# ethernet.net
KiCad netlist of a schematic drawn in Altium Designer
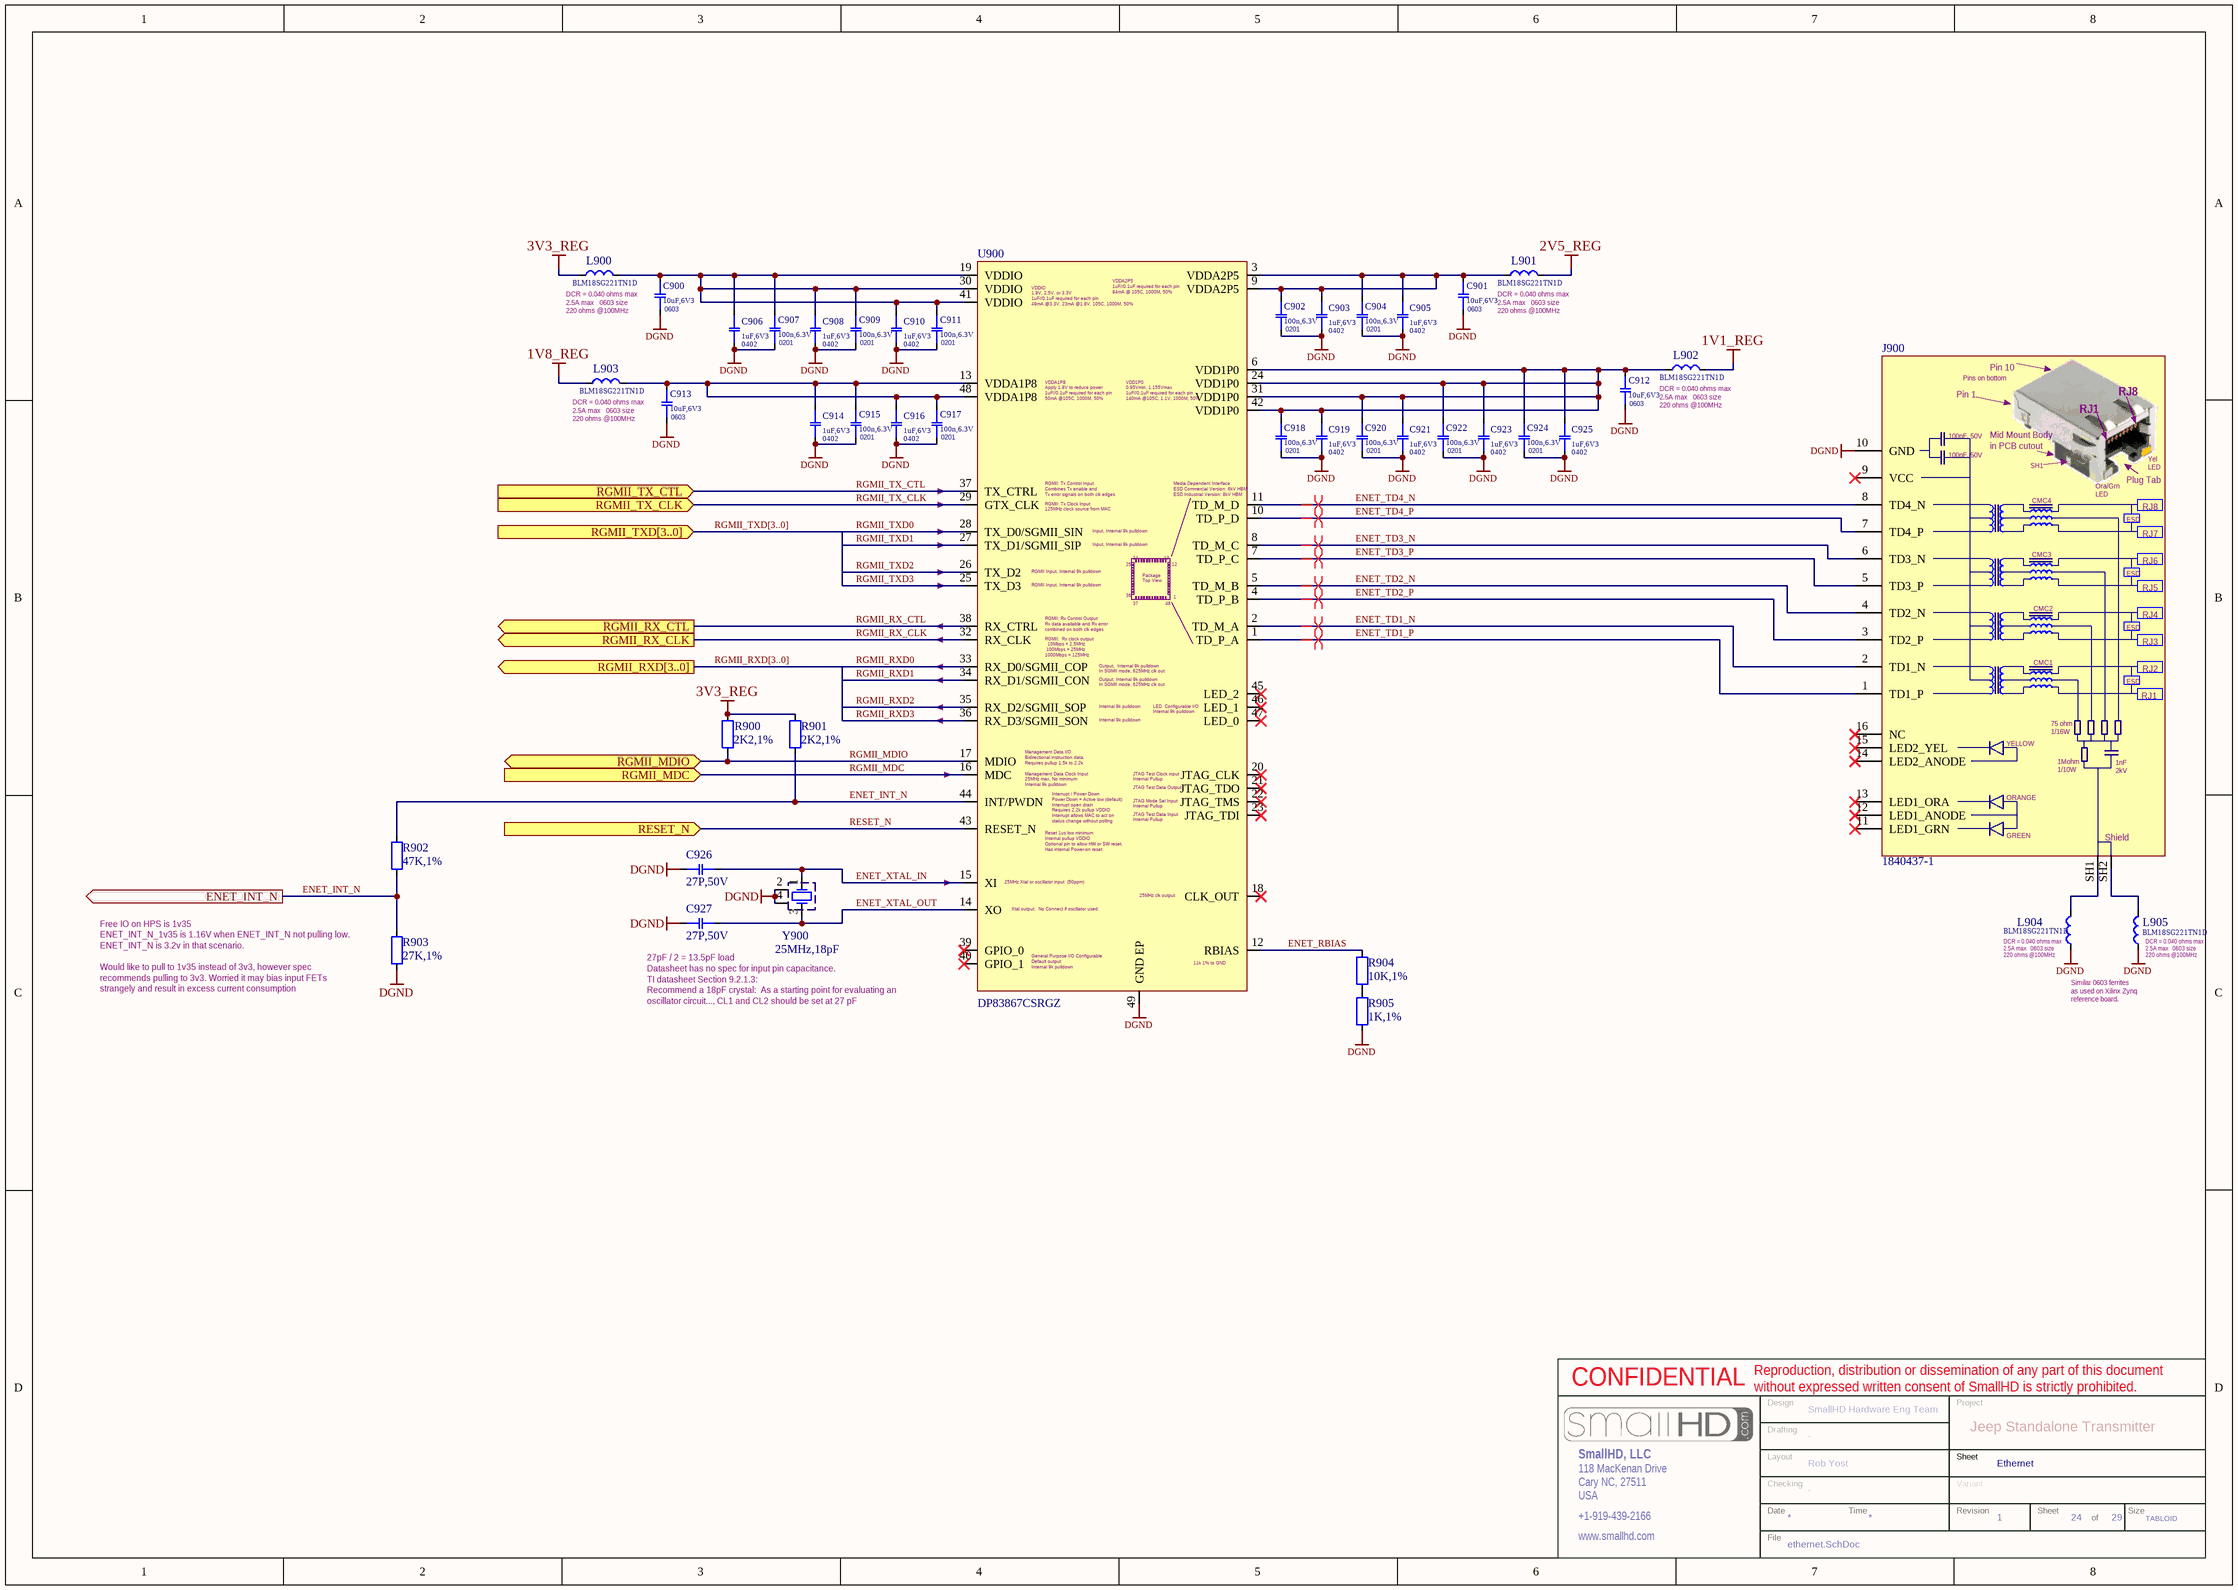
[diagram p0: ethernet.SchDoc]

(export (version "E")
  (design (tool "Eeschema 10.0.6"))
  (components
    (comp (ref "C900")
      (value "10uF,6V3")
      (footprint "CAPC1608X10N_0603")
      (description "CAP CER 10UF 6.3V 20% X5R 0603")
      (fields
        (field (name "MANUFACTURER") "TDK")
        (field (name "TOLERANCE") "20%")
        (field (name "DISPLAY FOOTPRINT") "0603")
      )
      (libsource (lib "smallHD") (part "CAP-NP_1"))
    )
    (comp (ref "C901")
      (value "10uF,6V3")
      (footprint "CAPC1608X10N_0603")
      (description "CAP CER 10UF 6.3V 20% X5R 0603")
      (fields
        (field (name "MANUFACTURER") "TDK")
        (field (name "TOLERANCE") "20%")
        (field (name "DISPLAY FOOTPRINT") "0603")
      )
      (libsource (lib "smallHD") (part "CAP-NP_1"))
    )
    (comp (ref "C902")
      (value "100n,6.3V")
      (footprint "CAPC0603X03L_0201")
      (description "CAP CER 0.1UF 6.3V 20% X5R 0201")
      (fields
        (field (name "MANUFACTURER") "TDK")
        (field (name "TOLERANCE") "20%")
        (field (name "DISPLAY FOOTPRINT") "0201")
      )
      (libsource (lib "smallHD") (part "CAP-NP_1"))
    )
    (comp (ref "C903")
      (value "1uF,6V3")
      (footprint "CAPC1005X06N_0402")
      (description "CAP CER 1UF 6.3V 10% X5R 0402")
      (fields
        (field (name "MANUFACTURER") "AVX")
        (field (name "TOLERANCE") "10%")
        (field (name "DISPLAY FOOTPRINT") "0402")
      )
      (libsource (lib "smallHD") (part "CAP-NP_1"))
    )
    (comp (ref "C904")
      (value "100n,6.3V")
      (footprint "CAPC0603X03L_0201")
      (description "CAP CER 0.1UF 6.3V 20% X5R 0201")
      (fields
        (field (name "MANUFACTURER") "TDK")
        (field (name "TOLERANCE") "20%")
        (field (name "DISPLAY FOOTPRINT") "0201")
      )
      (libsource (lib "smallHD") (part "CAP-NP_1"))
    )
    (comp (ref "C905")
      (value "1uF,6V3")
      (footprint "CAPC1005X06N_0402")
      (description "CAP CER 1UF 6.3V 10% X5R 0402")
      (fields
        (field (name "MANUFACTURER") "AVX")
        (field (name "TOLERANCE") "10%")
        (field (name "DISPLAY FOOTPRINT") "0402")
      )
      (libsource (lib "smallHD") (part "CAP-NP_1"))
    )
    (comp (ref "C906")
      (value "1uF,6V3")
      (footprint "CAPC1005X06N_0402")
      (description "CAP CER 1UF 6.3V 10% X5R 0402")
      (fields
        (field (name "MANUFACTURER") "AVX")
        (field (name "TOLERANCE") "10%")
        (field (name "DISPLAY FOOTPRINT") "0402")
      )
      (libsource (lib "smallHD") (part "CAP-NP_1"))
    )
    (comp (ref "C907")
      (value "100n,6.3V")
      (footprint "CAPC0603X03L_0201")
      (description "CAP CER 0.1UF 6.3V 20% X5R 0201")
      (fields
        (field (name "MANUFACTURER") "TDK")
        (field (name "TOLERANCE") "20%")
        (field (name "DISPLAY FOOTPRINT") "0201")
      )
      (libsource (lib "smallHD") (part "CAP-NP_1"))
    )
    (comp (ref "C908")
      (value "1uF,6V3")
      (footprint "CAPC1005X06N_0402")
      (description "CAP CER 1UF 6.3V 10% X5R 0402")
      (fields
        (field (name "MANUFACTURER") "AVX")
        (field (name "TOLERANCE") "10%")
        (field (name "DISPLAY FOOTPRINT") "0402")
      )
      (libsource (lib "smallHD") (part "CAP-NP_1"))
    )
    (comp (ref "C909")
      (value "100n,6.3V")
      (footprint "CAPC0603X03L_0201")
      (description "CAP CER 0.1UF 6.3V 20% X5R 0201")
      (fields
        (field (name "MANUFACTURER") "TDK")
        (field (name "TOLERANCE") "20%")
        (field (name "DISPLAY FOOTPRINT") "0201")
      )
      (libsource (lib "smallHD") (part "CAP-NP_1"))
    )
    (comp (ref "C910")
      (value "1uF,6V3")
      (footprint "CAPC1005X06N_0402")
      (description "CAP CER 1UF 6.3V 10% X5R 0402")
      (fields
        (field (name "MANUFACTURER") "AVX")
        (field (name "TOLERANCE") "10%")
        (field (name "DISPLAY FOOTPRINT") "0402")
      )
      (libsource (lib "smallHD") (part "CAP-NP_1"))
    )
    (comp (ref "C911")
      (value "100n,6.3V")
      (footprint "CAPC0603X03L_0201")
      (description "CAP CER 0.1UF 6.3V 20% X5R 0201")
      (fields
        (field (name "MANUFACTURER") "TDK")
        (field (name "TOLERANCE") "20%")
        (field (name "DISPLAY FOOTPRINT") "0201")
      )
      (libsource (lib "smallHD") (part "CAP-NP_1"))
    )
    (comp (ref "C912")
      (value "10uF,6V3")
      (footprint "CAPC1608X10N_0603")
      (description "CAP CER 10UF 6.3V 20% X5R 0603")
      (fields
        (field (name "MANUFACTURER") "TDK")
        (field (name "TOLERANCE") "20%")
        (field (name "DISPLAY FOOTPRINT") "0603")
      )
      (libsource (lib "smallHD") (part "CAP-NP_1"))
    )
    (comp (ref "C913")
      (value "10uF,6V3")
      (footprint "CAPC1608X10N_0603")
      (description "CAP CER 10UF 6.3V 20% X5R 0603")
      (fields
        (field (name "MANUFACTURER") "TDK")
        (field (name "TOLERANCE") "20%")
        (field (name "DISPLAY FOOTPRINT") "0603")
      )
      (libsource (lib "smallHD") (part "CAP-NP_1"))
    )
    (comp (ref "C914")
      (value "1uF,6V3")
      (footprint "CAPC1005X06N_0402")
      (description "CAP CER 1UF 6.3V 10% X5R 0402")
      (fields
        (field (name "MANUFACTURER") "AVX")
        (field (name "TOLERANCE") "10%")
        (field (name "DISPLAY FOOTPRINT") "0402")
      )
      (libsource (lib "smallHD") (part "CAP-NP_1"))
    )
    (comp (ref "C915")
      (value "100n,6.3V")
      (footprint "CAPC0603X03L_0201")
      (description "CAP CER 0.1UF 6.3V 20% X5R 0201")
      (fields
        (field (name "MANUFACTURER") "TDK")
        (field (name "TOLERANCE") "20%")
        (field (name "DISPLAY FOOTPRINT") "0201")
      )
      (libsource (lib "smallHD") (part "CAP-NP_1"))
    )
    (comp (ref "C916")
      (value "1uF,6V3")
      (footprint "CAPC1005X06N_0402")
      (description "CAP CER 1UF 6.3V 10% X5R 0402")
      (fields
        (field (name "MANUFACTURER") "AVX")
        (field (name "TOLERANCE") "10%")
        (field (name "DISPLAY FOOTPRINT") "0402")
      )
      (libsource (lib "smallHD") (part "CAP-NP_1"))
    )
    (comp (ref "C917")
      (value "100n,6.3V")
      (footprint "CAPC0603X03L_0201")
      (description "CAP CER 0.1UF 6.3V 20% X5R 0201")
      (fields
        (field (name "MANUFACTURER") "TDK")
        (field (name "TOLERANCE") "20%")
        (field (name "DISPLAY FOOTPRINT") "0201")
      )
      (libsource (lib "smallHD") (part "CAP-NP_1"))
    )
    (comp (ref "C918")
      (value "100n,6.3V")
      (footprint "CAPC0603X03L_0201")
      (description "CAP CER 0.1UF 6.3V 20% X5R 0201")
      (fields
        (field (name "MANUFACTURER") "TDK")
        (field (name "TOLERANCE") "20%")
        (field (name "DISPLAY FOOTPRINT") "0201")
      )
      (libsource (lib "smallHD") (part "CAP-NP_1"))
    )
    (comp (ref "C919")
      (value "1uF,6V3")
      (footprint "CAPC1005X06N_0402")
      (description "CAP CER 1UF 6.3V 10% X5R 0402")
      (fields
        (field (name "MANUFACTURER") "AVX")
        (field (name "TOLERANCE") "10%")
        (field (name "DISPLAY FOOTPRINT") "0402")
      )
      (libsource (lib "smallHD") (part "CAP-NP_1"))
    )
    (comp (ref "C920")
      (value "100n,6.3V")
      (footprint "CAPC0603X03L_0201")
      (description "CAP CER 0.1UF 6.3V 20% X5R 0201")
      (fields
        (field (name "MANUFACTURER") "TDK")
        (field (name "TOLERANCE") "20%")
        (field (name "DISPLAY FOOTPRINT") "0201")
      )
      (libsource (lib "smallHD") (part "CAP-NP_1"))
    )
    (comp (ref "C921")
      (value "1uF,6V3")
      (footprint "CAPC1005X06N_0402")
      (description "CAP CER 1UF 6.3V 10% X5R 0402")
      (fields
        (field (name "MANUFACTURER") "AVX")
        (field (name "TOLERANCE") "10%")
        (field (name "DISPLAY FOOTPRINT") "0402")
      )
      (libsource (lib "smallHD") (part "CAP-NP_1"))
    )
    (comp (ref "C922")
      (value "100n,6.3V")
      (footprint "CAPC0603X03L_0201")
      (description "CAP CER 0.1UF 6.3V 20% X5R 0201")
      (fields
        (field (name "MANUFACTURER") "TDK")
        (field (name "TOLERANCE") "20%")
        (field (name "DISPLAY FOOTPRINT") "0201")
      )
      (libsource (lib "smallHD") (part "CAP-NP_1"))
    )
    (comp (ref "C923")
      (value "1uF,6V3")
      (footprint "CAPC1005X06N_0402")
      (description "CAP CER 1UF 6.3V 10% X5R 0402")
      (fields
        (field (name "MANUFACTURER") "AVX")
        (field (name "TOLERANCE") "10%")
        (field (name "DISPLAY FOOTPRINT") "0402")
      )
      (libsource (lib "smallHD") (part "CAP-NP_1"))
    )
    (comp (ref "C924")
      (value "100n,6.3V")
      (footprint "CAPC0603X03L_0201")
      (description "CAP CER 0.1UF 6.3V 20% X5R 0201")
      (fields
        (field (name "MANUFACTURER") "TDK")
        (field (name "TOLERANCE") "20%")
        (field (name "DISPLAY FOOTPRINT") "0201")
      )
      (libsource (lib "smallHD") (part "CAP-NP_1"))
    )
    (comp (ref "C925")
      (value "1uF,6V3")
      (footprint "CAPC1005X06N_0402")
      (description "CAP CER 1UF 6.3V 10% X5R 0402")
      (fields
        (field (name "MANUFACTURER") "AVX")
        (field (name "TOLERANCE") "10%")
        (field (name "DISPLAY FOOTPRINT") "0402")
      )
      (libsource (lib "smallHD") (part "CAP-NP_1"))
    )
    (comp (ref "C926")
      (value "27P,50V")
      (footprint "CAPC0603X03L_0201")
      (description "CAP CER 27PF 50V 5% NPO 0201")
      (fields (field (name "MANUFACTURER") "Murata") (field (name "TOLERANCE") "5%"))
      (libsource (lib "smallHD") (part "CAP-NP_1"))
    )
    (comp (ref "C927")
      (value "27P,50V")
      (footprint "CAPC0603X03L_0201")
      (description "CAP CER 27PF 50V 5% NPO 0201")
      (fields (field (name "MANUFACTURER") "Murata") (field (name "TOLERANCE") "5%"))
      (libsource (lib "smallHD") (part "CAP-NP_1"))
    )
    (comp (ref "J900")
      (value "1840437-1")
      (footprint "BEL_1840437-1")
      (description "CONN RJ45 MAGJACK 1PORT 1000 BASE-T")
      (fields (field (name "MANUFACTURER") "Bel Fuse, Inc."))
      (libsource (lib "smallHD") (part "Bel_1840437-1"))
    )
    (comp (ref "L900")
      (value "BLM18SG221TN1D​")
      (footprint "INDC1608X10N_0603")
      (description "FERRITE CHIP 220 OHM 2.5A 0603")
      (fields (field (name "MANUFACTURER") "Murata"))
      (libsource (lib "smallHD") (part "INDUCTOR_1"))
    )
    (comp (ref "L901")
      (value "BLM18SG221TN1D​")
      (footprint "INDC1608X10N_0603")
      (description "FERRITE CHIP 220 OHM 2.5A 0603")
      (fields (field (name "MANUFACTURER") "Murata"))
      (libsource (lib "smallHD") (part "INDUCTOR_1"))
    )
    (comp (ref "L902")
      (value "BLM18SG221TN1D​")
      (footprint "INDC1608X10N_0603")
      (description "FERRITE CHIP 220 OHM 2.5A 0603")
      (fields (field (name "MANUFACTURER") "Murata"))
      (libsource (lib "smallHD") (part "INDUCTOR_1"))
    )
    (comp (ref "L903")
      (value "BLM18SG221TN1D​")
      (footprint "INDC1608X10N_0603")
      (description "FERRITE CHIP 220 OHM 2.5A 0603")
      (fields (field (name "MANUFACTURER") "Murata"))
      (libsource (lib "smallHD") (part "INDUCTOR_1"))
    )
    (comp (ref "L904")
      (value "BLM18SG221TN1D​")
      (footprint "INDC1608X10N_0603")
      (description "FERRITE CHIP 220 OHM 2.5A 0603")
      (fields (field (name "MANUFACTURER") "Murata"))
      (libsource (lib "smallHD") (part "INDUCTOR_1"))
    )
    (comp (ref "L905")
      (value "BLM18SG221TN1D​")
      (footprint "INDC1608X10N_0603")
      (description "FERRITE CHIP 220 OHM 2.5A 0603")
      (fields (field (name "MANUFACTURER") "Murata"))
      (libsource (lib "smallHD") (part "INDUCTOR_1"))
    )
    (comp (ref "R900")
      (value "2K2,1%")
      (footprint "RESC1005X04N_0402")
      (description "RES SMD 2.2K OHM 1/16W 1% 0402")
      (fields (field (name "MANUFACTURER") "Yageo") (field (name "POWER") "0.0625W"))
      (libsource (lib "smallHD") (part "RESISTOR_1"))
    )
    (comp (ref "R901")
      (value "2K2,1%")
      (footprint "RESC1005X04N_0402")
      (description "RES SMD 2.2K OHM 1/16W 1% 0402")
      (fields (field (name "MANUFACTURER") "Yageo") (field (name "POWER") "0.0625W"))
      (libsource (lib "smallHD") (part "RESISTOR_1"))
    )
    (comp (ref "R902")
      (value "47K,1%")
      (footprint "RESC1005X04N_0402")
      (description "RES SMD 47K OHM 1/16W 1% 0402")
      (fields (field (name "MANUFACTURER") "Yageo") (field (name "POWER") "0.0625W"))
      (libsource (lib "smallHD") (part "RESISTOR_1"))
    )
    (comp (ref "R903")
      (value "27K,1%")
      (footprint "RESC1005X04N_0402")
      (description "RES SMD 27K OHM 1/16W 1% 0402")
      (fields (field (name "MANUFACTURER") "Yageo") (field (name "POWER") "0.0625W"))
      (libsource (lib "smallHD") (part "RESISTOR_1"))
    )
    (comp (ref "R904")
      (value "10K,1%")
      (footprint "RESC1005X04N_0402")
      (description "RES SMD 10K OHM 1/16W 1% 0402")
      (fields (field (name "MANUFACTURER") "Yageo") (field (name "POWER") "0.0625W"))
      (libsource (lib "smallHD") (part "RESISTOR_1"))
    )
    (comp (ref "R905")
      (value "1K,1%")
      (footprint "RESC1005X04N_0402")
      (description "RES SMD 1K OHM 1/16W 1% 0402")
      (fields (field (name "MANUFACTURER") "Yageo") (field (name "POWER") "0.0625W"))
      (libsource (lib "") (part "RESISTOR_1_1"))
    )
    (comp (ref "U900")
      (value "DP83867CSRGZ")
      (footprint "QFN50P700X700X100_HS-49N")
      (description "IC ETHERNET PHY 10/100/1000 RGMII SGMII 48VQFN")
      (fields
        (field (name "MANUFACTURER") "Texas Instruments")
        (field (name "MANUFACTURER-2 PART NUMBER") "DP83867ISRGZ")
      )
      (libsource (lib "smallHD") (part "DP83867CS"))
    )
    (comp (ref "Y900")
      (value "25MHz,18pF")
      (footprint "XTAL_ABM8")
      (description "CRYSTAL 25.000MHZ 18PF SMD")
      (fields
        (field (name "MANUFACTURER") "Abracon Corporation")
        (field (name "MANUFACTURER PART NUMBER") "ABM8-25.000MHZ-B2-T")
      )
      (libsource (lib "smallHD") (part "XTAL_2"))
    )
  )
  (nets
    (net (code "1") (name "/ENET_INT_N") (class "Default")
      (node (ref "R901") (pin "1") (pinfunction "1_1") (pintype "passive"))
      (node (ref "R902") (pin "1") (pinfunction "1_1") (pintype "passive"))
      (node (ref "R902") (pin "2") (pinfunction "2_2") (pintype "passive"))
      (node (ref "R903") (pin "2") (pinfunction "2_2") (pintype "passive"))
      (node (ref "U900") (pin "44") (pinfunction "INT/PWDN_44") (pintype "passive"))
    )
    (net (code "2") (name "/ENET_RBIAS") (class "Default")
      (node (ref "R904") (pin "2") (pinfunction "2_2") (pintype "passive"))
      (node (ref "U900") (pin "12") (pinfunction "RBIAS_12") (pintype "passive"))
    )
    (net (code "3") (name "/ENET_TD1_N") (class "Default")
      (node (ref "J900") (pin "2") (pinfunction "TD1_N_2") (pintype "passive"))
      (node (ref "U900") (pin "2") (pinfunction "TD_M_A_2") (pintype "passive"))
    )
    (net (code "4") (name "/ENET_TD1_P") (class "Default")
      (node (ref "J900") (pin "1") (pinfunction "TD1_P_1") (pintype "passive"))
      (node (ref "U900") (pin "1") (pinfunction "TD_P_A_1") (pintype "passive"))
    )
    (net (code "5") (name "/ENET_TD2_N") (class "Default")
      (node (ref "J900") (pin "4") (pinfunction "TD2_N_4") (pintype "passive"))
      (node (ref "U900") (pin "5") (pinfunction "TD_M_B_5") (pintype "passive"))
    )
    (net (code "6") (name "/ENET_TD2_P") (class "Default")
      (node (ref "J900") (pin "3") (pinfunction "TD2_P_3") (pintype "passive"))
      (node (ref "U900") (pin "4") (pinfunction "TD_P_B_4") (pintype "passive"))
    )
    (net (code "7") (name "/ENET_TD3_N") (class "Default")
      (node (ref "J900") (pin "6") (pinfunction "TD3_N_6") (pintype "passive"))
      (node (ref "U900") (pin "8") (pinfunction "TD_M_C_8") (pintype "passive"))
    )
    (net (code "8") (name "/ENET_TD3_P") (class "Default")
      (node (ref "J900") (pin "5") (pinfunction "TD3_P_5") (pintype "passive"))
      (node (ref "U900") (pin "7") (pinfunction "TD_P_C_7") (pintype "passive"))
    )
    (net (code "9") (name "/ENET_TD4_N") (class "Default")
      (node (ref "J900") (pin "8") (pinfunction "TD4_N_8") (pintype "passive"))
      (node (ref "U900") (pin "11") (pinfunction "TD_M_D_11") (pintype "passive"))
    )
    (net (code "10") (name "/ENET_TD4_P") (class "Default")
      (node (ref "J900") (pin "7") (pinfunction "TD4_P_7") (pintype "passive"))
      (node (ref "U900") (pin "10") (pinfunction "TD_P_D_10") (pintype "passive"))
    )
    (net (code "11") (name "/ENET_XTAL_IN") (class "Default")
      (node (ref "C926") (pin "2") (pinfunction "2_2") (pintype "passive"))
      (node (ref "U900") (pin "15") (pinfunction "XI_15") (pintype "passive"))
      (node (ref "Y900") (pin "1") (pinfunction "1_1") (pintype "passive"))
    )
    (net (code "12") (name "/ENET_XTAL_OUT") (class "Default")
      (node (ref "C927") (pin "2") (pinfunction "2_2") (pintype "passive"))
      (node (ref "U900") (pin "14") (pinfunction "XO_14") (pintype "passive"))
      (node (ref "Y900") (pin "3") (pinfunction "3_3") (pintype "passive"))
    )
    (net (code "13") (name "/RESET_N") (class "Default")
      (node (ref "U900") (pin "43") (pinfunction "RESET_N_43") (pintype "passive"))
    )
    (net (code "14") (name "/RGMII_MDC") (class "Default")
      (node (ref "U900") (pin "16") (pinfunction "MDC_16") (pintype "passive"))
    )
    (net (code "15") (name "/RGMII_MDIO") (class "Default")
      (node (ref "R900") (pin "1") (pinfunction "1_1") (pintype "passive"))
      (node (ref "U900") (pin "17") (pinfunction "MDIO_17") (pintype "passive"))
    )
    (net (code "16") (name "/RGMII_RXD0") (class "Default")
      (node (ref "U900") (pin "33") (pinfunction "RX_D0/SGMII_COP_33") (pintype "passive"))
    )
    (net (code "17") (name "/RGMII_RXD1") (class "Default")
      (node (ref "U900") (pin "34") (pinfunction "RX_D1/SGMII_CON_34") (pintype "passive"))
    )
    (net (code "18") (name "/RGMII_RXD2") (class "Default")
      (node (ref "U900") (pin "35") (pinfunction "RX_D2/SGMII_SOP_35") (pintype "passive"))
    )
    (net (code "19") (name "/RGMII_RXD3") (class "Default")
      (node (ref "U900") (pin "36") (pinfunction "RX_D3/SGMII_SON_36") (pintype "passive"))
    )
    (net (code "21") (name "/RGMII_RX_CLK") (class "Default")
      (node (ref "U900") (pin "32") (pinfunction "RX_CLK_32") (pintype "passive"))
    )
    (net (code "22") (name "/RGMII_RX_CTL") (class "Default")
      (node (ref "U900") (pin "38") (pinfunction "RX_CTRL_38") (pintype "passive"))
    )
    (net (code "23") (name "/RGMII_TXD0") (class "Default")
      (node (ref "U900") (pin "28") (pinfunction "TX_D0/SGMII_SIN_28") (pintype "passive"))
    )
    (net (code "24") (name "/RGMII_TXD1") (class "Default")
      (node (ref "U900") (pin "27") (pinfunction "TX_D1/SGMII_SIP_27") (pintype "passive"))
    )
    (net (code "25") (name "/RGMII_TXD2") (class "Default")
      (node (ref "U900") (pin "26") (pinfunction "TX_D2_26") (pintype "passive"))
    )
    (net (code "26") (name "/RGMII_TXD3") (class "Default")
      (node (ref "U900") (pin "25") (pinfunction "TX_D3_25") (pintype "passive"))
    )
    (net (code "28") (name "/RGMII_TX_CLK") (class "Default")
      (node (ref "U900") (pin "29") (pinfunction "GTX_CLK_29") (pintype "passive"))
    )
    (net (code "29") (name "/RGMII_TX_CTL") (class "Default")
      (node (ref "U900") (pin "37") (pinfunction "TX_CTRL_37") (pintype "passive"))
    )
    (net (code "30") (name "1V1_REG") (class "Default")
      (node (ref "L902") (pin "2") (pinfunction "2_2") (pintype "passive"))
    )
    (net (code "31") (name "1V8_REG") (class "Default")
      (node (ref "L903") (pin "1") (pinfunction "1_1") (pintype "passive"))
    )
    (net (code "32") (name "2V5_REG") (class "Default")
      (node (ref "L901") (pin "2") (pinfunction "2_2") (pintype "passive"))
    )
    (net (code "33") (name "3V3_REG") (class "Default")
      (node (ref "L900") (pin "1") (pinfunction "1_1") (pintype "passive"))
      (node (ref "R900") (pin "2") (pinfunction "2_2") (pintype "passive"))
      (node (ref "R901") (pin "2") (pinfunction "2_2") (pintype "passive"))
    )
    (net (code "34") (name "DGND") (class "Default")
      (node (ref "C900") (pin "1") (pinfunction "1_1") (pintype "passive"))
      (node (ref "C901") (pin "1") (pinfunction "1_1") (pintype "passive"))
      (node (ref "C902") (pin "1") (pinfunction "1_1") (pintype "passive"))
      (node (ref "C903") (pin "1") (pinfunction "1_1") (pintype "passive"))
      (node (ref "C904") (pin "1") (pinfunction "1_1") (pintype "passive"))
      (node (ref "C905") (pin "1") (pinfunction "1_1") (pintype "passive"))
      (node (ref "C906") (pin "1") (pinfunction "1_1") (pintype "passive"))
      (node (ref "C907") (pin "1") (pinfunction "1_1") (pintype "passive"))
      (node (ref "C908") (pin "1") (pinfunction "1_1") (pintype "passive"))
      (node (ref "C909") (pin "1") (pinfunction "1_1") (pintype "passive"))
      (node (ref "C910") (pin "1") (pinfunction "1_1") (pintype "passive"))
      (node (ref "C911") (pin "1") (pinfunction "1_1") (pintype "passive"))
      (node (ref "C912") (pin "1") (pinfunction "1_1") (pintype "passive"))
      (node (ref "C913") (pin "1") (pinfunction "1_1") (pintype "passive"))
      (node (ref "C914") (pin "1") (pinfunction "1_1") (pintype "passive"))
      (node (ref "C915") (pin "1") (pinfunction "1_1") (pintype "passive"))
      (node (ref "C916") (pin "1") (pinfunction "1_1") (pintype "passive"))
      (node (ref "C917") (pin "1") (pinfunction "1_1") (pintype "passive"))
      (node (ref "C918") (pin "1") (pinfunction "1_1") (pintype "passive"))
      (node (ref "C919") (pin "1") (pinfunction "1_1") (pintype "passive"))
      (node (ref "C920") (pin "1") (pinfunction "1_1") (pintype "passive"))
      (node (ref "C921") (pin "1") (pinfunction "1_1") (pintype "passive"))
      (node (ref "C922") (pin "1") (pinfunction "1_1") (pintype "passive"))
      (node (ref "C923") (pin "1") (pinfunction "1_1") (pintype "passive"))
      (node (ref "C924") (pin "1") (pinfunction "1_1") (pintype "passive"))
      (node (ref "C925") (pin "1") (pinfunction "1_1") (pintype "passive"))
      (node (ref "C926") (pin "1") (pinfunction "1_1") (pintype "passive"))
      (node (ref "C927") (pin "1") (pinfunction "1_1") (pintype "passive"))
      (node (ref "J900") (pin "10") (pinfunction "GND_10") (pintype "passive"))
      (node (ref "L904") (pin "1") (pinfunction "1_1") (pintype "passive"))
      (node (ref "L905") (pin "1") (pinfunction "1_1") (pintype "passive"))
      (node (ref "R903") (pin "1") (pinfunction "1_1") (pintype "passive"))
      (node (ref "R905") (pin "2") (pinfunction "2_2") (pintype "passive"))
      (node (ref "U900") (pin "49") (pinfunction "GND_EP_49") (pintype "passive"))
      (node (ref "Y900") (pin "2") (pinfunction "2_2") (pintype "passive"))
      (node (ref "Y900") (pin "4") (pinfunction "4_4") (pintype "passive"))
    )
    (net (code "35") (name "Net-(C900-Pad2)") (class "Default")
      (node (ref "C900") (pin "2") (pinfunction "2_2") (pintype "passive"))
      (node (ref "C906") (pin "2") (pinfunction "2_2") (pintype "passive"))
      (node (ref "C907") (pin "2") (pinfunction "2_2") (pintype "passive"))
      (node (ref "C908") (pin "2") (pinfunction "2_2") (pintype "passive"))
      (node (ref "C909") (pin "2") (pinfunction "2_2") (pintype "passive"))
      (node (ref "C910") (pin "2") (pinfunction "2_2") (pintype "passive"))
      (node (ref "C911") (pin "2") (pinfunction "2_2") (pintype "passive"))
      (node (ref "L900") (pin "2") (pinfunction "2_2") (pintype "passive"))
      (node (ref "U900") (pin "19") (pinfunction "VDDIO_19") (pintype "passive"))
      (node (ref "U900") (pin "30") (pinfunction "VDDIO_30") (pintype "passive"))
      (node (ref "U900") (pin "41") (pinfunction "VDDIO_41") (pintype "passive"))
    )
    (net (code "36") (name "Net-(C901-Pad2)") (class "Default")
      (node (ref "C901") (pin "2") (pinfunction "2_2") (pintype "passive"))
      (node (ref "C902") (pin "2") (pinfunction "2_2") (pintype "passive"))
      (node (ref "C903") (pin "2") (pinfunction "2_2") (pintype "passive"))
      (node (ref "C904") (pin "2") (pinfunction "2_2") (pintype "passive"))
      (node (ref "C905") (pin "2") (pinfunction "2_2") (pintype "passive"))
      (node (ref "L901") (pin "1") (pinfunction "1_1") (pintype "passive"))
      (node (ref "U900") (pin "3") (pinfunction "VDDA2P5_3") (pintype "passive"))
      (node (ref "U900") (pin "9") (pinfunction "VDDA2P5_9") (pintype "passive"))
    )
    (net (code "37") (name "Net-(C912-Pad2)") (class "Default")
      (node (ref "C912") (pin "2") (pinfunction "2_2") (pintype "passive"))
      (node (ref "C918") (pin "2") (pinfunction "2_2") (pintype "passive"))
      (node (ref "C919") (pin "2") (pinfunction "2_2") (pintype "passive"))
      (node (ref "C920") (pin "2") (pinfunction "2_2") (pintype "passive"))
      (node (ref "C921") (pin "2") (pinfunction "2_2") (pintype "passive"))
      (node (ref "C922") (pin "2") (pinfunction "2_2") (pintype "passive"))
      (node (ref "C923") (pin "2") (pinfunction "2_2") (pintype "passive"))
      (node (ref "C924") (pin "2") (pinfunction "2_2") (pintype "passive"))
      (node (ref "C925") (pin "2") (pinfunction "2_2") (pintype "passive"))
      (node (ref "L902") (pin "1") (pinfunction "1_1") (pintype "passive"))
      (node (ref "U900") (pin "24") (pinfunction "VDD1P0_24") (pintype "passive"))
      (node (ref "U900") (pin "31") (pinfunction "VDD1P0_31") (pintype "passive"))
      (node (ref "U900") (pin "42") (pinfunction "VDD1P0_42") (pintype "passive"))
      (node (ref "U900") (pin "6") (pinfunction "VDD1P0_6") (pintype "passive"))
    )
    (net (code "38") (name "Net-(C913-Pad2)") (class "Default")
      (node (ref "C913") (pin "2") (pinfunction "2_2") (pintype "passive"))
      (node (ref "C914") (pin "2") (pinfunction "2_2") (pintype "passive"))
      (node (ref "C915") (pin "2") (pinfunction "2_2") (pintype "passive"))
      (node (ref "C916") (pin "2") (pinfunction "2_2") (pintype "passive"))
      (node (ref "C917") (pin "2") (pinfunction "2_2") (pintype "passive"))
      (node (ref "L903") (pin "2") (pinfunction "2_2") (pintype "passive"))
      (node (ref "U900") (pin "13") (pinfunction "VDDA1P8_13") (pintype "passive"))
      (node (ref "U900") (pin "48") (pinfunction "VDDA1P8_48") (pintype "passive"))
    )
    (net (code "39") (name "Net-(J900-A-PadSH1)") (class "Default")
      (node (ref "J900") (pin "SH1") (pinfunction "A_SH1") (pintype "passive"))
      (node (ref "L904") (pin "2") (pinfunction "2_2") (pintype "passive"))
    )
    (net (code "40") (name "Net-(J900-A-PadSH2)") (class "Default")
      (node (ref "J900") (pin "SH2") (pinfunction "A_SH2") (pintype "passive"))
      (node (ref "L905") (pin "2") (pinfunction "2_2") (pintype "passive"))
    )
    (net (code "41") (name "Net-(R904-Pad1)") (class "Default")
      (node (ref "R904") (pin "1") (pinfunction "1_1") (pintype "passive"))
      (node (ref "R905") (pin "1") (pinfunction "1_1") (pintype "passive"))
    )
    (net (code "42") (name "unconnected-(J900-LED1_ANODE-Pad12)") (class "Default")
      (node (ref "J900") (pin "12") (pinfunction "LED1_ANODE_12") (pintype "passive+no_connect"))
    )
    (net (code "43") (name "unconnected-(J900-LED1_GRN-Pad11)") (class "Default")
      (node (ref "J900") (pin "11") (pinfunction "LED1_GRN_11") (pintype "passive+no_connect"))
    )
    (net (code "44") (name "unconnected-(J900-LED1_ORA-Pad13)") (class "Default")
      (node (ref "J900") (pin "13") (pinfunction "LED1_ORA_13") (pintype "passive+no_connect"))
    )
    (net (code "45") (name "unconnected-(J900-LED2_ANODE-Pad14)") (class "Default")
      (node (ref "J900") (pin "14") (pinfunction "LED2_ANODE_14") (pintype "passive+no_connect"))
    )
    (net (code "46") (name "unconnected-(J900-LED2_YEL-Pad15)") (class "Default")
      (node (ref "J900") (pin "15") (pinfunction "LED2_YEL_15") (pintype "passive+no_connect"))
    )
    (net (code "47") (name "unconnected-(J900-NC-Pad16)") (class "Default")
      (node (ref "J900") (pin "16") (pinfunction "NC_16") (pintype "passive+no_connect"))
    )
    (net (code "48") (name "unconnected-(J900-VCC-Pad9)") (class "Default")
      (node (ref "J900") (pin "9") (pinfunction "VCC_9") (pintype "passive+no_connect"))
    )
    (net (code "49") (name "unconnected-(U900-CLK_OUT-Pad18)") (class "Default")
      (node (ref "U900") (pin "18") (pinfunction "CLK_OUT_18") (pintype "passive+no_connect"))
    )
    (net (code "50") (name "unconnected-(U900-GPIO_0-Pad39)") (class "Default")
      (node (ref "U900") (pin "39") (pinfunction "GPIO_0_39") (pintype "passive+no_connect"))
    )
    (net (code "51") (name "unconnected-(U900-GPIO_1-Pad40)") (class "Default")
      (node (ref "U900") (pin "40") (pinfunction "GPIO_1_40") (pintype "passive+no_connect"))
    )
    (net (code "52") (name "unconnected-(U900-JTAG_CLK-Pad20)") (class "Default")
      (node (ref "U900") (pin "20") (pinfunction "JTAG_CLK_20") (pintype "passive+no_connect"))
    )
    (net (code "53") (name "unconnected-(U900-JTAG_TDI-Pad23)") (class "Default")
      (node (ref "U900") (pin "23") (pinfunction "JTAG_TDI_23") (pintype "passive+no_connect"))
    )
    (net (code "54") (name "unconnected-(U900-JTAG_TDO-Pad21)") (class "Default")
      (node (ref "U900") (pin "21") (pinfunction "JTAG_TDO_21") (pintype "passive+no_connect"))
    )
    (net (code "55") (name "unconnected-(U900-JTAG_TMS-Pad22)") (class "Default")
      (node (ref "U900") (pin "22") (pinfunction "JTAG_TMS_22") (pintype "passive+no_connect"))
    )
    (net (code "56") (name "unconnected-(U900-LED_0-Pad47)") (class "Default")
      (node (ref "U900") (pin "47") (pinfunction "LED_0_47") (pintype "passive+no_connect"))
    )
    (net (code "57") (name "unconnected-(U900-LED_1-Pad46)") (class "Default")
      (node (ref "U900") (pin "46") (pinfunction "LED_1_46") (pintype "passive+no_connect"))
    )
    (net (code "58") (name "unconnected-(U900-LED_2-Pad45)") (class "Default")
      (node (ref "U900") (pin "45") (pinfunction "LED_2_45") (pintype "passive+no_connect"))
    )
  )
)
